# ASSIGNMENT.net
KiCad netlist of a schematic drawn in EAGLE
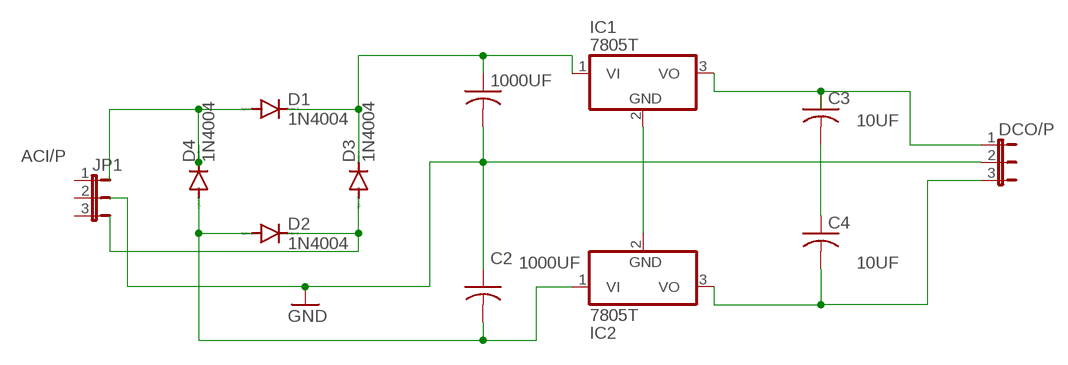
[diagram p0: schematic, sheet 1]

(export (version "E")
  (design (tool "Eeschema 10.0.6"))
  (components
    (comp (ref "1000UF")
      (value "C-US050-030X075")
      (footprint "eagle-import:C050-030X075")
      (libsource (lib "eagle-import") (part "C-US050-030X075"))
    )
    (comp (ref "C2")
      (value "C-US050-030X075")
      (footprint "eagle-import:C050-030X075")
      (libsource (lib "eagle-import") (part "C-US050-030X075"))
    )
    (comp (ref "C3")
      (value "C-US050-030X075")
      (footprint "eagle-import:C050-030X075")
      (libsource (lib "eagle-import") (part "C-US050-030X075"))
    )
    (comp (ref "C4")
      (value "C-US050-030X075")
      (footprint "eagle-import:C050-030X075")
      (libsource (lib "eagle-import") (part "C-US050-030X075"))
    )
    (comp (ref "D1")
      (value "1N4004")
      (footprint "eagle-import:DO41-10")
      (libsource (lib "eagle-import") (part "1N4004"))
    )
    (comp (ref "D2")
      (value "1N4004")
      (footprint "eagle-import:DO41-10")
      (libsource (lib "eagle-import") (part "1N4004"))
    )
    (comp (ref "D3")
      (value "1N4004")
      (footprint "eagle-import:DO41-10")
      (libsource (lib "eagle-import") (part "1N4004"))
    )
    (comp (ref "D4")
      (value "1N4004")
      (footprint "eagle-import:DO41-10")
      (libsource (lib "eagle-import") (part "1N4004"))
    )
    (comp (ref "DCO/P")
      (value "JP2E")
      (footprint "eagle-import:JP2")
      (libsource (lib "eagle-import") (part "JP2E"))
    )
    (comp (ref "IC1")
      (value "7805T")
      (footprint "eagle-import:TO220H")
      (libsource (lib "eagle-import") (part "78T05"))
    )
    (comp (ref "IC2")
      (value "7805T")
      (footprint "eagle-import:TO220H")
      (libsource (lib "eagle-import") (part "78T05"))
    )
    (comp (ref "JP1")
      (value "JP2E")
      (footprint "eagle-import:JP2")
      (libsource (lib "eagle-import") (part "JP2E"))
    )
  )
  (nets
    (net (code "1") (name "/10UF") (class "Default")
      (node (ref "C3") (pin "2") (pinfunction "2_2") (pintype "passive"))
      (node (ref "C4") (pin "1") (pinfunction "1_1") (pintype "passive"))
      (node (ref "C4") (pin "2") (pinfunction "2_2") (pintype "passive"))
      (node (ref "DCO/P") (pin "3") (pinfunction "3_3") (pintype "passive"))
      (node (ref "IC2") (pin "3") (pinfunction "VO_3") (pintype "passive"))
    )
    (net (code "2") (name "/1000UF") (class "Default")
      (node (ref "C2") (pin "2") (pinfunction "2_2") (pintype "passive"))
      (node (ref "D2") (pin "A") (pinfunction "A_A") (pintype "passive"))
      (node (ref "D4") (pin "A") (pinfunction "A_A") (pintype "passive"))
      (node (ref "IC2") (pin "1") (pinfunction "VI_1") (pintype "input"))
    )
    (net (code "3") (name "/ACI{slash}P") (class "Default")
      (node (ref "D1") (pin "A") (pinfunction "A_A") (pintype "passive"))
      (node (ref "D4") (pin "C") (pinfunction "C_C") (pintype "passive"))
    )
    (net (code "4") (name "GND") (class "Default")
      (node (ref "1000UF") (pin "2") (pinfunction "2_2") (pintype "passive"))
      (node (ref "C2") (pin "1") (pinfunction "1_1") (pintype "passive"))
      (node (ref "DCO/P") (pin "2") (pinfunction "2_2") (pintype "passive"))
    )
    (net (code "5") (name "Net-(D2-PadC)") (class "Default")
      (node (ref "D2") (pin "C") (pinfunction "C_C") (pintype "passive"))
      (node (ref "D3") (pin "A") (pinfunction "A_A") (pintype "passive"))
    )
    (net (code "6") (name "Net-(IC1-GND)") (class "Default")
      (node (ref "IC1") (pin "2") (pinfunction "GND_2") (pintype "passive"))
      (node (ref "IC2") (pin "2") (pinfunction "GND_2") (pintype "passive"))
    )
    (net (code "7") (name "Net-(IC1-VI)") (class "Default")
      (node (ref "1000UF") (pin "1") (pinfunction "1_1") (pintype "passive"))
      (node (ref "D1") (pin "C") (pinfunction "C_C") (pintype "passive"))
      (node (ref "D3") (pin "C") (pinfunction "C_C") (pintype "passive"))
      (node (ref "IC1") (pin "1") (pinfunction "VI_1") (pintype "input"))
    )
    (net (code "8") (name "Net-(IC1-VO)") (class "Default")
      (node (ref "C3") (pin "1") (pinfunction "1_1") (pintype "passive"))
      (node (ref "DCO/P") (pin "1") (pinfunction "1_1") (pintype "passive"))
      (node (ref "IC1") (pin "3") (pinfunction "VO_3") (pintype "passive"))
    )
    (net (code "9") (name "unconnected-(JP1-Pad1)") (class "Default")
      (node (ref "JP1") (pin "1") (pinfunction "1_1") (pintype "passive"))
    )
    (net (code "10") (name "unconnected-(JP1-Pad2)") (class "Default")
      (node (ref "JP1") (pin "2") (pinfunction "2_2") (pintype "passive"))
    )
    (net (code "11") (name "unconnected-(JP1-Pad3)") (class "Default")
      (node (ref "JP1") (pin "3") (pinfunction "3_3") (pintype "passive"))
    )
  )
)
